# STM32F407_CONTROLLER.net
KiCad netlist of a schematic drawn in Altium Designer
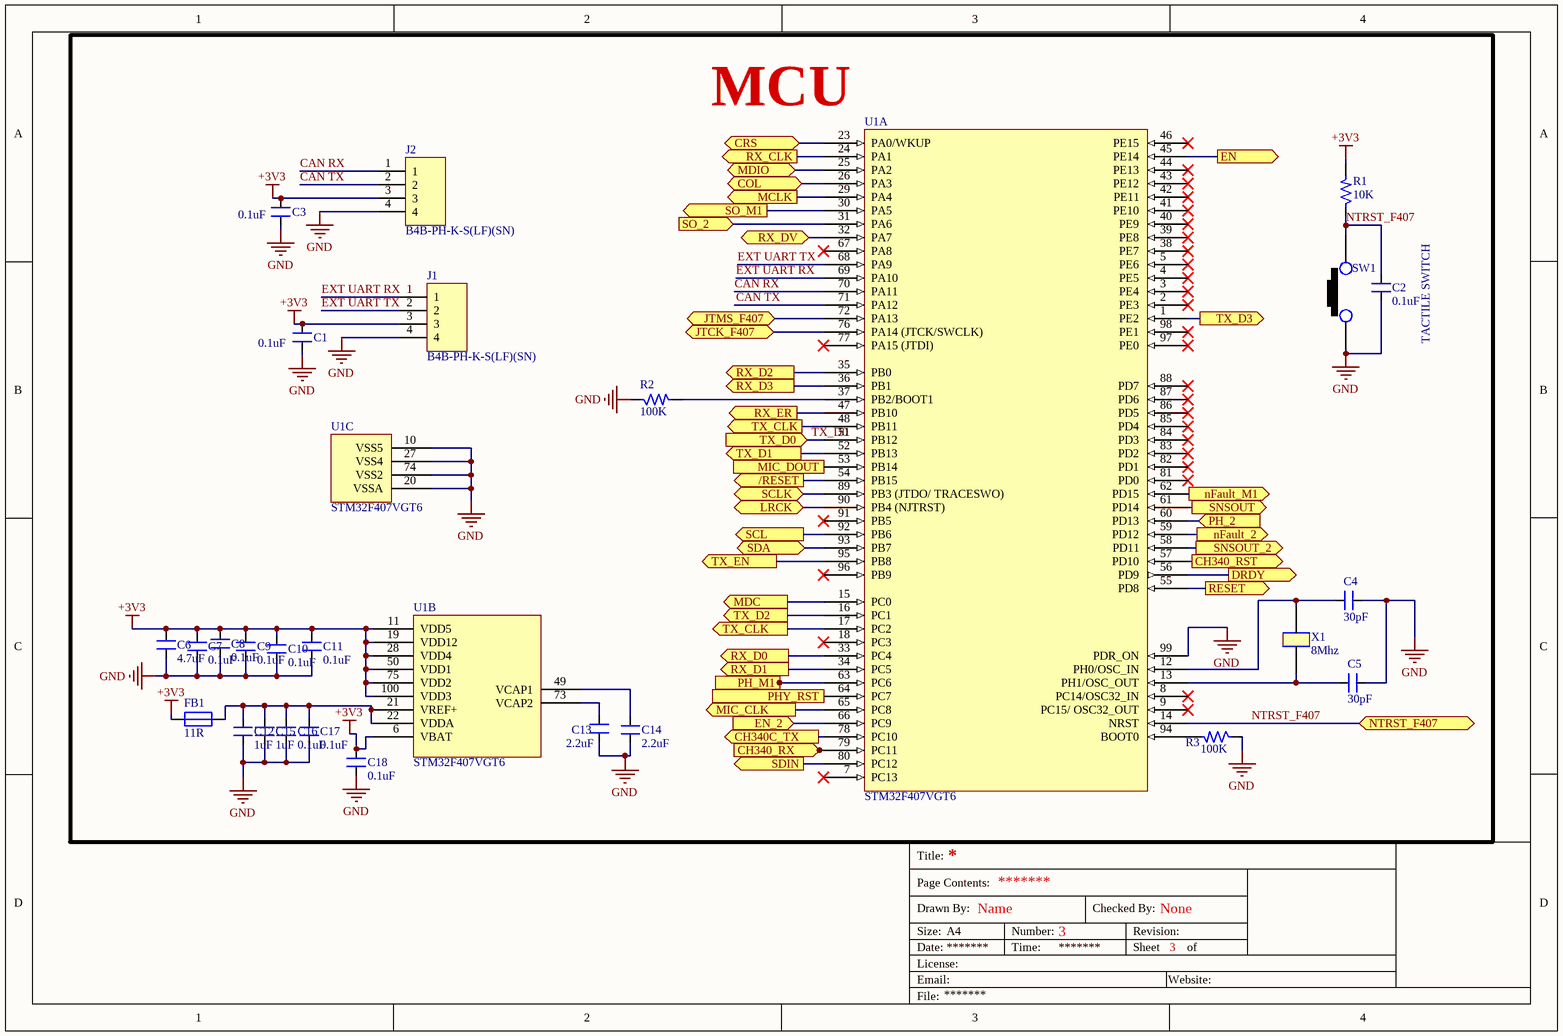
[diagram p0: STM32F407 CONTROLLER.SchDoc]

(export (version "E")
  (design (tool "Eeschema 10.0.6"))
  (components
    (comp (ref "C1")
      (value "0.1uF")
      (footprint "CAP_0805")
      (description "0.1µF ±5% 50V Ceramic Capacitor X7R 0805 (2012 Metric)")
      (fields
        (field (name "MANUFACTURER") "AVX Corporation")
        (field (name "MANUFACTURER PART NUMBER") "08055C104JAT4A")
      )
      (libsource (lib "ESTEEMPCBLIB") (part "CAP_0.1uF-50V-5%-0805"))
    )
    (comp (ref "C2")
      (value "0.1uF")
      (footprint "CAP_0805")
      (description "0.1µF ±5% 50V Ceramic Capacitor X7R 0805 (2012 Metric)")
      (fields
        (field (name "MANUFACTURER") "AVX Corporation")
        (field (name "MANUFACTURER PART NUMBER") "08055C104JAT4A")
      )
      (libsource (lib "ESTEEMPCBLIB") (part "CAP_0.1uF-50V-5%-0805"))
    )
    (comp (ref "C3")
      (value "0.1uF")
      (footprint "CAP_0805")
      (description "0.1µF ±5% 50V Ceramic Capacitor X7R 0805 (2012 Metric)")
      (fields
        (field (name "MANUFACTURER") "AVX Corporation")
        (field (name "MANUFACTURER PART NUMBER") "08055C104JAT4A")
      )
      (libsource (lib "ESTEEMPCBLIB") (part "CAP_0.1uF-50V-5%-0805"))
    )
    (comp (ref "C4")
      (value "30pF")
      (footprint "CAP_0805")
      (description "±10% 50V Ceramic Capacitor C0G, NP0 0805 (2012 Metric)")
      (fields
        (field (name "MANUFACTURER PART NUMBER") "C0805C300K5GAC7800")
        (field (name "MANUFACTURER") "KEMET")
      )
      (libsource (lib "ESTEEMPCBLIB") (part "CAP_30pF-50V-10%-0805"))
    )
    (comp (ref "C5")
      (value "30pF")
      (footprint "CAP_0805")
      (description "±10% 50V Ceramic Capacitor C0G, NP0 0805 (2012 Metric)")
      (fields
        (field (name "MANUFACTURER PART NUMBER") "C0805C300K5GAC7800")
        (field (name "MANUFACTURER") "KEMET")
      )
      (libsource (lib "ESTEEMPCBLIB") (part "CAP_30pF-50V-10%-0805"))
    )
    (comp (ref "C6")
      (value "4.7uF")
      (footprint "CAP_0805")
      (description "4.7µF ±10% 50V Ceramic Capacitor X5R 0805 (2012 Metric)")
      (fields
        (field (name "MANUFACTURER") "Yageo")
        (field (name "MANUFACTURER PART NUMBER") "GRM21BR61H475KE51L")
      )
      (libsource (lib "ESTEEMPCBLIB") (part "CAP_4.7uF-50V-10%-0805"))
    )
    (comp (ref "C7")
      (value "0.1uF")
      (footprint "CAP_0805")
      (description "0.1µF ±10% 50V Ceramic Capacitor X7R 0805 (2012 Metric)")
      (fields
        (field (name "MANUFACTURER") "Samsung")
        (field (name "MANUFACTURER PART NUMBER") "CL21B104KBCNNNC")
      )
      (libsource (lib "ESTEEMPCBLIB") (part "CAP_0.1uF-50V-10%-0805"))
    )
    (comp (ref "C8")
      (value "0.1uF")
      (footprint "CAP_0805")
      (description "0.1µF ±10% 50V Ceramic Capacitor X7R 0805 (2012 Metric)")
      (fields
        (field (name "MANUFACTURER") "Samsung")
        (field (name "MANUFACTURER PART NUMBER") "CL21B104KBCNNNC")
      )
      (libsource (lib "ESTEEMPCBLIB") (part "CAP_0.1uF-50V-10%-0805"))
    )
    (comp (ref "C9")
      (value "0.1uF")
      (footprint "CAP_0805")
      (description "0.1µF ±10% 50V Ceramic Capacitor X7R 0805 (2012 Metric)")
      (fields
        (field (name "MANUFACTURER") "Samsung")
        (field (name "MANUFACTURER PART NUMBER") "CL21B104KBCNNNC")
      )
      (libsource (lib "ESTEEMPCBLIB") (part "CAP_0.1uF-50V-10%-0805"))
    )
    (comp (ref "C10")
      (value "0.1uF")
      (footprint "CAP_0805")
      (description "0.1µF ±10% 50V Ceramic Capacitor X7R 0805 (2012 Metric)")
      (fields
        (field (name "MANUFACTURER") "Samsung")
        (field (name "MANUFACTURER PART NUMBER") "CL21B104KBCNNNC")
      )
      (libsource (lib "ESTEEMPCBLIB") (part "CAP_0.1uF-50V-10%-0805"))
    )
    (comp (ref "C11")
      (value "0.1uF")
      (footprint "CAP_0805")
      (description "0.1µF ±10% 50V Ceramic Capacitor X7R 0805 (2012 Metric)")
      (fields
        (field (name "MANUFACTURER") "Samsung")
        (field (name "MANUFACTURER PART NUMBER") "CL21B104KBCNNNC")
      )
      (libsource (lib "ESTEEMPCBLIB") (part "CAP_0.1uF-50V-10%-0805"))
    )
    (comp (ref "C12")
      (value "1uF")
      (footprint "CAP_0805")
      (description "1µF ±5% 50V Ceramic Capacitor X7R 0805 (2012 Metric)")
      (fields
        (field (name "MANUFACTURER") "Samsung")
        (field (name "MANUFACTURER PART NUMBER") "CC0805JKX7R9BB105")
      )
      (libsource (lib "ESTEEMPCBLIB") (part "CAP_1uF-50V-5%-0805"))
    )
    (comp (ref "C13")
      (value "2.2uF")
      (footprint "CAP_0805")
      (description "2.2µF ±10% 25V Ceramic Capacitor X7R 0805 (2012 Metric)")
      (fields
        (field (name "MANUFACTURER") "KEMET")
        (field (name "MANUFACTURER PART NUMBER") "CL21B225KAFNFNE")
      )
      (libsource (lib "ESTEEMPCBLIB") (part "CAP_2.2uF-25V-10%-0805"))
    )
    (comp (ref "C14")
      (value "2.2uF")
      (footprint "CAP_0805")
      (description "2.2µF ±10% 25V Ceramic Capacitor X7R 0805 (2012 Metric)")
      (fields
        (field (name "MANUFACTURER") "KEMET")
        (field (name "MANUFACTURER PART NUMBER") "CL21B225KAFNFNE")
      )
      (libsource (lib "ESTEEMPCBLIB") (part "CAP_2.2uF-25V-10%-0805"))
    )
    (comp (ref "C15")
      (value "1uF")
      (footprint "CAP_0805")
      (description "1µF ±5% 50V Ceramic Capacitor X7R 0805 (2012 Metric)")
      (fields
        (field (name "MANUFACTURER") "Samsung")
        (field (name "MANUFACTURER PART NUMBER") "CC0805JKX7R9BB105")
      )
      (libsource (lib "ESTEEMPCBLIB") (part "CAP_1uF-50V-5%-0805"))
    )
    (comp (ref "C16")
      (value "0.1uF")
      (footprint "CAP_0805")
      (description "0.1µF ±10% 50V Ceramic Capacitor X7R 0805 (2012 Metric)")
      (fields
        (field (name "MANUFACTURER") "Samsung")
        (field (name "MANUFACTURER PART NUMBER") "CL21B104KBCNNNC")
      )
      (libsource (lib "ESTEEMPCBLIB") (part "CAP_0.1uF-50V-10%-0805"))
    )
    (comp (ref "C17")
      (value "0.1uF")
      (footprint "CAP_0805")
      (description "0.1µF ±10% 50V Ceramic Capacitor X7R 0805 (2012 Metric)")
      (fields
        (field (name "MANUFACTURER") "Samsung")
        (field (name "MANUFACTURER PART NUMBER") "CL21B104KBCNNNC")
      )
      (libsource (lib "ESTEEMPCBLIB") (part "CAP_0.1uF-50V-10%-0805"))
    )
    (comp (ref "C18")
      (value "0.1uF")
      (footprint "CAP_0805")
      (description "0.1µF ±10% 50V Ceramic Capacitor X7R 0805 (2012 Metric)")
      (fields
        (field (name "MANUFACTURER") "Samsung")
        (field (name "MANUFACTURER PART NUMBER") "CL21B104KBCNNNC")
      )
      (libsource (lib "ESTEEMPCBLIB") (part "CAP_0.1uF-50V-10%-0805"))
    )
    (comp (ref "FB1")
      (value "11R")
      (footprint "IND_0805")
      (description "11 Ohms @ 100MHz 1 Power Line Ferrite Bead 0805 (2012 Metric) 1.5A 60mOhm")
      (fields
        (field (name "MANUFACTURER") "Murata")
        (field (name "MANUFACTURER PART NUMBER") "MI0805K110R-10")
      )
      (libsource (lib "ESTEEMPCBLIB") (part "FB_11R-100MHZ-1.5A-0805"))
    )
    (comp (ref "J1")
      (value "B4B-PH-K-S(LF)(SN)")
      (footprint "CON4_78_B4B-PH-K-S(LF)(SN)")
      (description "Connector Header Through Hole 4 position 0.079\" (2.00mm)")
      (fields (field (name "MANUFACTURER") "JST") (field (name "MATING PART NUMBER") "PHR-4"))
      (libsource (lib "ESTEEMPCBLIB") (part "CON-PLG_4X1-78-ST-TH"))
    )
    (comp (ref "J2")
      (value "B4B-PH-K-S(LF)(SN)")
      (footprint "CON4_78_B4B-PH-K-S(LF)(SN)")
      (description "Connector Header Through Hole 4 position 0.079\" (2.00mm)")
      (fields (field (name "MANUFACTURER") "JST") (field (name "MATING PART NUMBER") "PHR-4"))
      (libsource (lib "ESTEEMPCBLIB") (part "CON-PLG_4X1-78-ST-TH"))
    )
    (comp (ref "R1")
      (value "10K")
      (footprint "RES_0805")
      (description "10 kOhms ±1% 0.125W, 1/8W Chip Resistor 0805 (2012 Metric) Automotive AEC-Q200 Thick Film")
      (fields (field (name "MANUFACTURER") "CTS") (field (name "MANUFACTURER PART NUMBER") "WR08X1002FTL"))
      (libsource (lib "ESTEEMPCBLIB") (part "RES_10K-0.125W-1%-0805"))
    )
    (comp (ref "R2")
      (value "100K")
      (footprint "RES_0805")
      (description "100 kOhms ±1% 0.125W, 1/8W Chip Resistor 0805 (2012 Metric) Automotive AEC-Q200 Thick Film")
      (fields (field (name "MANUFACTURER") "Walsin") (field (name "MANUFACTURER PART NUMBER") "WR08X1003FTL"))
      (libsource (lib "ESTEEMPCBLIB") (part "RES_100K-0.125W-1%-0805"))
    )
    (comp (ref "R3")
      (value "100K")
      (footprint "RES_0805")
      (description "100 kOhms ±1% 0.125W, 1/8W Chip Resistor 0805 (2012 Metric) Automotive AEC-Q200 Thick Film")
      (fields (field (name "MANUFACTURER") "Walsin") (field (name "MANUFACTURER PART NUMBER") "WR08X1003FTL"))
      (libsource (lib "ESTEEMPCBLIB") (part "RES_100K-0.125W-1%-0805"))
    )
    (comp (ref "SW1")
      (value "TACTILE SWITCH")
      (footprint "SW_342_SMD")
      (description "Tactile Switch SPST-NO Top Actuated Surface Mount")
      (fields
        (field (name "MANUFACTURER") "ITT C&K")
        (field (name "MANUFACTURER PART NUMBER") "RS-282G05A3-SMRT")
      )
      (libsource (lib "ESTEEMPCBLIB") (part "SW1_RS-282G05A3-SMRT-SMD"))
    )
    (comp (ref "U1")
      (value "STM32F407VGT6")
      (footprint "QFN100_19.6_669_58X10_SMD")
      (description "ARM® Cortex®-M4 STM32F4 Microcontroller IC 32-Bit 168MHz 1MB (1M x 8) FLASH 100-LQFP (14x14)")
      (fields (field (name "MANUFACTURER") "STMicroelectronics"))
      (libsource (lib "ESTEEMPCBLIB") (part "IC_STM32F407VGT6"))
    )
    (comp (ref "X1")
      (value "8Mhz")
      (footprint "XTAL_314_240X47_SMD")
      (description "8MHz ±30ppm Crystal 32pF 60 Ohms HC-49/US")
      (fields
        (field (name "MANUFACTURER") "Fox Electronics")
        (field (name "MANUFACTURER PART NUMBER") "ECS-80-32-5PX-TR")
      )
      (libsource (lib "ESTEEMPCBLIB") (part "XTAL_8MHZ-ECS-80-32-5PX-SMD"))
    )
  )
  (nets
    (net (code "1") (name "+3V3") (class "Default")
      (node (ref "C1") (pin "2") (pinfunction "2_2") (pintype "passive"))
      (node (ref "C10") (pin "2") (pinfunction "2_2") (pintype "passive"))
      (node (ref "C11") (pin "2") (pinfunction "2_2") (pintype "passive"))
      (node (ref "C18") (pin "2") (pinfunction "2_2") (pintype "passive"))
      (node (ref "C3") (pin "2") (pinfunction "2_2") (pintype "passive"))
      (node (ref "C6") (pin "2") (pinfunction "2_2") (pintype "passive"))
      (node (ref "C7") (pin "2") (pinfunction "2_2") (pintype "passive"))
      (node (ref "C8") (pin "2") (pinfunction "2_2") (pintype "passive"))
      (node (ref "C9") (pin "2") (pinfunction "2_2") (pintype "passive"))
      (node (ref "FB1") (pin "1") (pinfunction "1_1") (pintype "passive"))
      (node (ref "J1") (pin "3") (pinfunction "3_3") (pintype "passive"))
      (node (ref "J2") (pin "3") (pinfunction "3_3") (pintype "passive"))
      (node (ref "R1") (pin "2") (pinfunction "2_2") (pintype "passive"))
      (node (ref "U1") (pin "100") (pinfunction "VDD3_100") (pintype "passive"))
      (node (ref "U1") (pin "11") (pinfunction "VDD5_11") (pintype "passive"))
      (node (ref "U1") (pin "19") (pinfunction "VDD12_19") (pintype "passive"))
      (node (ref "U1") (pin "28") (pinfunction "VDD4_28") (pintype "passive"))
      (node (ref "U1") (pin "50") (pinfunction "VDD1_50") (pintype "passive"))
      (node (ref "U1") (pin "6") (pinfunction "VBAT_6") (pintype "passive"))
      (node (ref "U1") (pin "75") (pinfunction "VDD2_75") (pintype "passive"))
    )
    (net (code "2") (name "/CAN RX") (class "Default")
      (node (ref "J2") (pin "1") (pinfunction "1_1") (pintype "passive"))
      (node (ref "U1") (pin "70") (pinfunction "PA11_70") (pintype "input"))
    )
    (net (code "3") (name "/CAN TX") (class "Default")
      (node (ref "J2") (pin "2") (pinfunction "2_2") (pintype "passive"))
      (node (ref "U1") (pin "71") (pinfunction "PA12_71") (pintype "input"))
    )
    (net (code "4") (name "/CH340C_TX") (class "Default")
      (node (ref "U1") (pin "78") (pinfunction "PC10_78") (pintype "input"))
    )
    (net (code "5") (name "/CH340_RST") (class "Default")
      (node (ref "U1") (pin "57") (pinfunction "PD10_57") (pintype "input"))
    )
    (net (code "6") (name "/CH340_RX") (class "Default")
      (node (ref "U1") (pin "79") (pinfunction "PC11_79") (pintype "input"))
    )
    (net (code "7") (name "/COL") (class "Default")
      (node (ref "U1") (pin "26") (pinfunction "PA3_26") (pintype "input"))
    )
    (net (code "8") (name "/CRS") (class "Default")
      (node (ref "U1") (pin "23") (pinfunction "PA0/WKUP_23") (pintype "input"))
    )
    (net (code "9") (name "/DRDY") (class "Default")
      (node (ref "U1") (pin "56") (pinfunction "PD9_56") (pintype "input"))
    )
    (net (code "10") (name "/EN") (class "Default")
      (node (ref "U1") (pin "45") (pinfunction "PE14_45") (pintype "input"))
    )
    (net (code "11") (name "/EN_2") (class "Default")
      (node (ref "U1") (pin "66") (pinfunction "PC9_66") (pintype "input"))
    )
    (net (code "12") (name "/EXT UART RX") (class "Default")
      (node (ref "J1") (pin "1") (pinfunction "1_1") (pintype "passive"))
      (node (ref "U1") (pin "69") (pinfunction "PA10_69") (pintype "input"))
    )
    (net (code "13") (name "/EXT UART TX") (class "Default")
      (node (ref "J1") (pin "2") (pinfunction "2_2") (pintype "passive"))
      (node (ref "U1") (pin "68") (pinfunction "PA9_68") (pintype "input"))
    )
    (net (code "14") (name "/JTCK_F407") (class "Default")
      (node (ref "U1") (pin "76") (pinfunction "PA14_(JTCK/SWCLK)_76") (pintype "input"))
    )
    (net (code "15") (name "/JTMS_F407") (class "Default")
      (node (ref "U1") (pin "72") (pinfunction "PA13_72") (pintype "input"))
    )
    (net (code "16") (name "/LRCK") (class "Default")
      (node (ref "U1") (pin "90") (pinfunction "PB4_(NJTRST)_90") (pintype "input"))
    )
    (net (code "17") (name "/MCLK") (class "Default")
      (node (ref "U1") (pin "29") (pinfunction "PA4_29") (pintype "input"))
    )
    (net (code "18") (name "/MDC") (class "Default")
      (node (ref "U1") (pin "15") (pinfunction "PC0_15") (pintype "input"))
    )
    (net (code "19") (name "/MDIO") (class "Default")
      (node (ref "U1") (pin "25") (pinfunction "PA2_25") (pintype "input"))
    )
    (net (code "20") (name "/MIC_CLK") (class "Default")
      (node (ref "U1") (pin "65") (pinfunction "PC8_65") (pintype "input"))
    )
    (net (code "21") (name "/MIC_DOUT") (class "Default")
      (node (ref "U1") (pin "53") (pinfunction "PB14_53") (pintype "input"))
    )
    (net (code "22") (name "/NTRST_F407") (class "Default")
      (node (ref "C2") (pin "2") (pinfunction "2_2") (pintype "passive"))
      (node (ref "R1") (pin "1") (pinfunction "1_1") (pintype "passive"))
      (node (ref "SW1") (pin "2") (pinfunction "2_2") (pintype "passive"))
      (node (ref "U1") (pin "14") (pinfunction "NRST_14") (pintype "input"))
    )
    (net (code "23") (name "/PHY_RST") (class "Default")
      (node (ref "U1") (pin "64") (pinfunction "PC7_64") (pintype "input"))
    )
    (net (code "24") (name "/PH_2") (class "Default")
      (node (ref "U1") (pin "60") (pinfunction "PD13_60") (pintype "input"))
    )
    (net (code "25") (name "/PH_M1") (class "Default")
      (node (ref "U1") (pin "63") (pinfunction "PC6_63") (pintype "input"))
    )
    (net (code "26") (name "/RESET") (class "Default")
      (node (ref "U1") (pin "55") (pinfunction "PD8_55") (pintype "input"))
    )
    (net (code "27") (name "/RX_CLK") (class "Default")
      (node (ref "U1") (pin "24") (pinfunction "PA1_24") (pintype "input"))
    )
    (net (code "28") (name "/RX_D0") (class "Default")
      (node (ref "U1") (pin "33") (pinfunction "PC4_33") (pintype "input"))
    )
    (net (code "29") (name "/RX_D1") (class "Default")
      (node (ref "U1") (pin "34") (pinfunction "PC5_34") (pintype "input"))
    )
    (net (code "30") (name "/RX_D2") (class "Default")
      (node (ref "U1") (pin "35") (pinfunction "PB0_35") (pintype "input"))
    )
    (net (code "31") (name "/RX_D3") (class "Default")
      (node (ref "U1") (pin "36") (pinfunction "PB1_36") (pintype "input"))
    )
    (net (code "32") (name "/RX_DV") (class "Default")
      (node (ref "U1") (pin "32") (pinfunction "PA7_32") (pintype "input"))
    )
    (net (code "33") (name "/RX_ER") (class "Default")
      (node (ref "U1") (pin "47") (pinfunction "PB10_47") (pintype "input"))
    )
    (net (code "34") (name "/SCL") (class "Default")
      (node (ref "U1") (pin "92") (pinfunction "PB6_92") (pintype "input"))
    )
    (net (code "35") (name "/SCLK") (class "Default")
      (node (ref "U1") (pin "89") (pinfunction "PB3_(JTDO/_TRACESWO)_89") (pintype "input"))
    )
    (net (code "36") (name "/SDA") (class "Default")
      (node (ref "U1") (pin "93") (pinfunction "PB7_93") (pintype "input"))
    )
    (net (code "37") (name "/SDIN") (class "Default")
      (node (ref "U1") (pin "80") (pinfunction "PC12_80") (pintype "input"))
    )
    (net (code "38") (name "/SNSOUT") (class "Default")
      (node (ref "U1") (pin "61") (pinfunction "PD14_61") (pintype "input"))
    )
    (net (code "39") (name "/SNSOUT_2") (class "Default")
      (node (ref "U1") (pin "58") (pinfunction "PD11_58") (pintype "input"))
    )
    (net (code "40") (name "/SO_2") (class "Default")
      (node (ref "U1") (pin "31") (pinfunction "PA6_31") (pintype "input"))
    )
    (net (code "41") (name "/SO_M1") (class "Default")
      (node (ref "U1") (pin "30") (pinfunction "PA5_30") (pintype "input"))
    )
    (net (code "42") (name "/TX_CLK") (class "Default")
      (node (ref "U1") (pin "17") (pinfunction "PC2_17") (pintype "input"))
      (node (ref "U1") (pin "48") (pinfunction "PB11_48") (pintype "input"))
    )
    (net (code "43") (name "/TX_D0") (class "Default")
      (node (ref "U1") (pin "51") (pinfunction "PB12_51") (pintype "input"))
    )
    (net (code "44") (name "/TX_D1") (class "Default")
      (node (ref "U1") (pin "52") (pinfunction "PB13_52") (pintype "input"))
    )
    (net (code "45") (name "/TX_D2") (class "Default")
      (node (ref "U1") (pin "16") (pinfunction "PC1_16") (pintype "input"))
    )
    (net (code "46") (name "/TX_D3") (class "Default")
      (node (ref "U1") (pin "1") (pinfunction "PE2_1") (pintype "input"))
    )
    (net (code "47") (name "/TX_EN") (class "Default")
      (node (ref "U1") (pin "95") (pinfunction "PB8_95") (pintype "input"))
    )
    (net (code "48") (name "/nFault_2") (class "Default")
      (node (ref "U1") (pin "59") (pinfunction "PD12_59") (pintype "input"))
    )
    (net (code "49") (name "/nFault_M1") (class "Default")
      (node (ref "U1") (pin "62") (pinfunction "PD15_62") (pintype "input"))
    )
    (net (code "50") (name "/{slash}RESET") (class "Default")
      (node (ref "U1") (pin "54") (pinfunction "PB15_54") (pintype "input"))
    )
    (net (code "51") (name "GND") (class "Default")
      (node (ref "C1") (pin "1") (pinfunction "1_1") (pintype "passive"))
      (node (ref "C10") (pin "1") (pinfunction "1_1") (pintype "passive"))
      (node (ref "C11") (pin "1") (pinfunction "1_1") (pintype "passive"))
      (node (ref "C12") (pin "1") (pinfunction "1_1") (pintype "passive"))
      (node (ref "C13") (pin "1") (pinfunction "1_1") (pintype "passive"))
      (node (ref "C14") (pin "1") (pinfunction "1_1") (pintype "passive"))
      (node (ref "C15") (pin "1") (pinfunction "1_1") (pintype "passive"))
      (node (ref "C16") (pin "1") (pinfunction "1_1") (pintype "passive"))
      (node (ref "C17") (pin "1") (pinfunction "1_1") (pintype "passive"))
      (node (ref "C18") (pin "1") (pinfunction "1_1") (pintype "passive"))
      (node (ref "C2") (pin "1") (pinfunction "1_1") (pintype "passive"))
      (node (ref "C3") (pin "1") (pinfunction "1_1") (pintype "passive"))
      (node (ref "C4") (pin "2") (pinfunction "2_2") (pintype "passive"))
      (node (ref "C5") (pin "2") (pinfunction "2_2") (pintype "passive"))
      (node (ref "C6") (pin "1") (pinfunction "1_1") (pintype "passive"))
      (node (ref "C7") (pin "1") (pinfunction "1_1") (pintype "passive"))
      (node (ref "C8") (pin "1") (pinfunction "1_1") (pintype "passive"))
      (node (ref "C9") (pin "1") (pinfunction "1_1") (pintype "passive"))
      (node (ref "J1") (pin "4") (pinfunction "4_4") (pintype "passive"))
      (node (ref "J2") (pin "4") (pinfunction "4_4") (pintype "passive"))
      (node (ref "R2") (pin "1") (pinfunction "1_1") (pintype "passive"))
      (node (ref "R3") (pin "1") (pinfunction "1_1") (pintype "passive"))
      (node (ref "SW1") (pin "1") (pinfunction "1_1") (pintype "passive"))
      (node (ref "U1") (pin "10") (pinfunction "VSS5_10") (pintype "passive"))
      (node (ref "U1") (pin "20") (pinfunction "VSSA_20") (pintype "passive"))
      (node (ref "U1") (pin "27") (pinfunction "VSS4_27") (pintype "passive"))
      (node (ref "U1") (pin "74") (pinfunction "VSS2_74") (pintype "passive"))
      (node (ref "U1") (pin "99") (pinfunction "PDR_ON_99") (pintype "input"))
    )
    (net (code "52") (name "Net-(U1A-BOOT0)") (class "Default")
      (node (ref "R3") (pin "2") (pinfunction "2_2") (pintype "passive"))
      (node (ref "U1") (pin "94") (pinfunction "BOOT0_94") (pintype "input"))
    )
    (net (code "53") (name "Net-(U1A-PB2{slash}BOOT1)") (class "Default")
      (node (ref "R2") (pin "2") (pinfunction "2_2") (pintype "passive"))
      (node (ref "U1") (pin "37") (pinfunction "PB2/BOOT1_37") (pintype "input"))
    )
    (net (code "54") (name "Net-(U1A-PH0{slash}OSC_IN)") (class "Default")
      (node (ref "C4") (pin "1") (pinfunction "1_1") (pintype "passive"))
      (node (ref "U1") (pin "12") (pinfunction "PH0/OSC_IN_12") (pintype "input"))
      (node (ref "X1") (pin "2") (pinfunction "2_2") (pintype "passive"))
    )
    (net (code "55") (name "Net-(U1A-PH1{slash}OSC_OUT)") (class "Default")
      (node (ref "C5") (pin "1") (pinfunction "1_1") (pintype "passive"))
      (node (ref "U1") (pin "13") (pinfunction "PH1/OSC_OUT_13") (pintype "input"))
      (node (ref "X1") (pin "1") (pinfunction "1_1") (pintype "passive"))
    )
    (net (code "56") (name "Net-(U1B-VCAP1)") (class "Default")
      (node (ref "C14") (pin "2") (pinfunction "2_2") (pintype "passive"))
      (node (ref "U1") (pin "49") (pinfunction "VCAP1_49") (pintype "passive"))
    )
    (net (code "57") (name "Net-(U1B-VCAP2)") (class "Default")
      (node (ref "C13") (pin "2") (pinfunction "2_2") (pintype "passive"))
      (node (ref "U1") (pin "73") (pinfunction "VCAP2_73") (pintype "passive"))
    )
    (net (code "58") (name "Net-(U1B-VDDA)") (class "Default")
      (node (ref "C12") (pin "2") (pinfunction "2_2") (pintype "passive"))
      (node (ref "C15") (pin "2") (pinfunction "2_2") (pintype "passive"))
      (node (ref "C16") (pin "2") (pinfunction "2_2") (pintype "passive"))
      (node (ref "C17") (pin "2") (pinfunction "2_2") (pintype "passive"))
      (node (ref "FB1") (pin "2") (pinfunction "2_2") (pintype "passive"))
      (node (ref "U1") (pin "21") (pinfunction "VREF+_21") (pintype "passive"))
      (node (ref "U1") (pin "22") (pinfunction "VDDA_22") (pintype "passive"))
    )
    (net (code "59") (name "unconnected-(U1A-PA8-Pad67)") (class "Default")
      (node (ref "U1") (pin "67") (pinfunction "PA8_67") (pintype "input+no_connect"))
    )
    (net (code "60") (name "unconnected-(U1A-PA15_(JTDI)-Pad77)") (class "Default")
      (node (ref "U1") (pin "77") (pinfunction "PA15_(JTDI)_77") (pintype "input+no_connect"))
    )
    (net (code "61") (name "unconnected-(U1A-PB5-Pad91)") (class "Default")
      (node (ref "U1") (pin "91") (pinfunction "PB5_91") (pintype "input+no_connect"))
    )
    (net (code "62") (name "unconnected-(U1A-PB9-Pad96)") (class "Default")
      (node (ref "U1") (pin "96") (pinfunction "PB9_96") (pintype "input+no_connect"))
    )
    (net (code "63") (name "unconnected-(U1A-PC3-Pad18)") (class "Default")
      (node (ref "U1") (pin "18") (pinfunction "PC3_18") (pintype "input+no_connect"))
    )
    (net (code "64") (name "unconnected-(U1A-PC13-Pad7)") (class "Default")
      (node (ref "U1") (pin "7") (pinfunction "PC13_7") (pintype "input+no_connect"))
    )
    (net (code "65") (name "unconnected-(U1A-PC14{slash}OSC32_IN-Pad8)") (class "Default")
      (node (ref "U1") (pin "8") (pinfunction "PC14/OSC32_IN_8") (pintype "input+no_connect"))
    )
    (net (code "66") (name "unconnected-(U1A-PC15{slash}_OSC32_OUT-Pad9)") (class "Default")
      (node (ref "U1") (pin "9") (pinfunction "PC15/_OSC32_OUT_9") (pintype "input+no_connect"))
    )
    (net (code "67") (name "unconnected-(U1A-PD0-Pad81)") (class "Default")
      (node (ref "U1") (pin "81") (pinfunction "PD0_81") (pintype "input+no_connect"))
    )
    (net (code "68") (name "unconnected-(U1A-PD1-Pad82)") (class "Default")
      (node (ref "U1") (pin "82") (pinfunction "PD1_82") (pintype "input+no_connect"))
    )
    (net (code "69") (name "unconnected-(U1A-PD2-Pad83)") (class "Default")
      (node (ref "U1") (pin "83") (pinfunction "PD2_83") (pintype "input+no_connect"))
    )
    (net (code "70") (name "unconnected-(U1A-PD3-Pad84)") (class "Default")
      (node (ref "U1") (pin "84") (pinfunction "PD3_84") (pintype "input+no_connect"))
    )
    (net (code "71") (name "unconnected-(U1A-PD4-Pad85)") (class "Default")
      (node (ref "U1") (pin "85") (pinfunction "PD4_85") (pintype "input+no_connect"))
    )
    (net (code "72") (name "unconnected-(U1A-PD5-Pad86)") (class "Default")
      (node (ref "U1") (pin "86") (pinfunction "PD5_86") (pintype "input+no_connect"))
    )
    (net (code "73") (name "unconnected-(U1A-PD6-Pad87)") (class "Default")
      (node (ref "U1") (pin "87") (pinfunction "PD6_87") (pintype "input+no_connect"))
    )
    (net (code "74") (name "unconnected-(U1A-PD7-Pad88)") (class "Default")
      (node (ref "U1") (pin "88") (pinfunction "PD7_88") (pintype "input+no_connect"))
    )
    (net (code "75") (name "unconnected-(U1A-PE0-Pad97)") (class "Default")
      (node (ref "U1") (pin "97") (pinfunction "PE0_97") (pintype "input+no_connect"))
    )
    (net (code "76") (name "unconnected-(U1A-PE1-Pad98)") (class "Default")
      (node (ref "U1") (pin "98") (pinfunction "PE1_98") (pintype "input+no_connect"))
    )
    (net (code "77") (name "unconnected-(U1A-PE3-Pad2)") (class "Default")
      (node (ref "U1") (pin "2") (pinfunction "PE3_2") (pintype "input+no_connect"))
    )
    (net (code "78") (name "unconnected-(U1A-PE4-Pad3)") (class "Default")
      (node (ref "U1") (pin "3") (pinfunction "PE4_3") (pintype "input+no_connect"))
    )
    (net (code "79") (name "unconnected-(U1A-PE5-Pad4)") (class "Default")
      (node (ref "U1") (pin "4") (pinfunction "PE5_4") (pintype "input+no_connect"))
    )
    (net (code "80") (name "unconnected-(U1A-PE6-Pad5)") (class "Default")
      (node (ref "U1") (pin "5") (pinfunction "PE6_5") (pintype "input+no_connect"))
    )
    (net (code "81") (name "unconnected-(U1A-PE7-Pad38)") (class "Default")
      (node (ref "U1") (pin "38") (pinfunction "PE7_38") (pintype "input+no_connect"))
    )
    (net (code "82") (name "unconnected-(U1A-PE8-Pad39)") (class "Default")
      (node (ref "U1") (pin "39") (pinfunction "PE8_39") (pintype "input+no_connect"))
    )
    (net (code "83") (name "unconnected-(U1A-PE9-Pad40)") (class "Default")
      (node (ref "U1") (pin "40") (pinfunction "PE9_40") (pintype "input+no_connect"))
    )
    (net (code "84") (name "unconnected-(U1A-PE10-Pad41)") (class "Default")
      (node (ref "U1") (pin "41") (pinfunction "PE10_41") (pintype "input+no_connect"))
    )
    (net (code "85") (name "unconnected-(U1A-PE11-Pad42)") (class "Default")
      (node (ref "U1") (pin "42") (pinfunction "PE11_42") (pintype "input+no_connect"))
    )
    (net (code "86") (name "unconnected-(U1A-PE12-Pad43)") (class "Default")
      (node (ref "U1") (pin "43") (pinfunction "PE12_43") (pintype "input+no_connect"))
    )
    (net (code "87") (name "unconnected-(U1A-PE13-Pad44)") (class "Default")
      (node (ref "U1") (pin "44") (pinfunction "PE13_44") (pintype "input+no_connect"))
    )
    (net (code "88") (name "unconnected-(U1A-PE15-Pad46)") (class "Default")
      (node (ref "U1") (pin "46") (pinfunction "PE15_46") (pintype "input+no_connect"))
    )
  )
)
